# HighVoltageOutputMirror.net
KiCad netlist of a schematic drawn in EAGLE
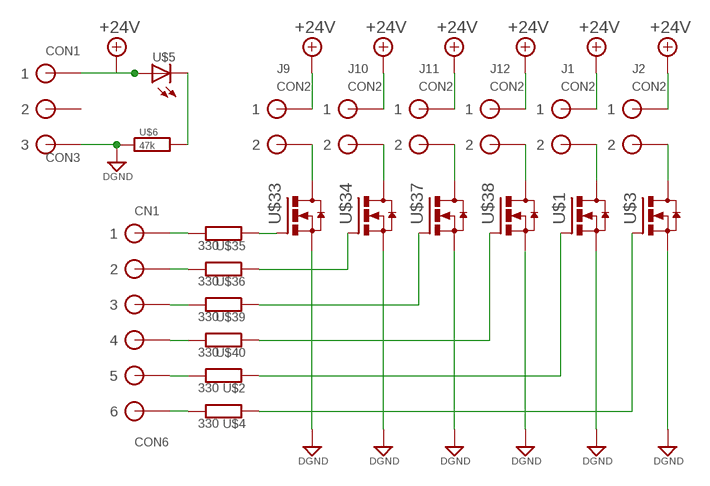
[diagram p0: schematic, sheet 1]

(export (version "E")
  (design (tool "Eeschema 10.0.6"))
  (components
    (comp (ref "CN1")
      (value "CON6")
      (footprint "eagle-import:CON6")
      (libsource (lib "eagle-import") (part "CON6"))
    )
    (comp (ref "CON1")
      (value "CON3")
      (footprint "eagle-import:CON3")
      (libsource (lib "eagle-import") (part "CON3"))
    )
    (comp (ref "J1")
      (value "CON2")
      (footprint "eagle-import:CON2")
      (libsource (lib "eagle-import") (part "CON2"))
    )
    (comp (ref "J2")
      (value "CON2")
      (footprint "eagle-import:CON2")
      (libsource (lib "eagle-import") (part "CON2"))
    )
    (comp (ref "J9")
      (value "CON2")
      (footprint "eagle-import:CON2")
      (libsource (lib "eagle-import") (part "CON2"))
    )
    (comp (ref "J10")
      (value "CON2")
      (footprint "eagle-import:CON2")
      (libsource (lib "eagle-import") (part "CON2"))
    )
    (comp (ref "J11")
      (value "CON2")
      (footprint "eagle-import:CON2")
      (libsource (lib "eagle-import") (part "CON2"))
    )
    (comp (ref "J12")
      (value "CON2")
      (footprint "eagle-import:CON2")
      (libsource (lib "eagle-import") (part "CON2"))
    )
    (comp (ref "U$1")
      (value "TO-252(MOS-FET_N)TO-252FORHAND")
      (footprint "eagle-import:TO-252FORHAND")
      (libsource (lib "eagle-import") (part "TO-252(MOS-FET_N)TO-252FORHAND"))
    )
    (comp (ref "U$2")
      (value "330")
      (footprint "eagle-import:1_4W-H4_(0207_10)")
      (libsource (lib "eagle-import") (part "抵抗0207/10"))
    )
    (comp (ref "U$3")
      (value "TO-252(MOS-FET_N)TO-252FORHAND")
      (footprint "eagle-import:TO-252FORHAND")
      (libsource (lib "eagle-import") (part "TO-252(MOS-FET_N)TO-252FORHAND"))
    )
    (comp (ref "U$4")
      (value "330")
      (footprint "eagle-import:1_4W-H4_(0207_10)")
      (libsource (lib "eagle-import") (part "抵抗0207/10"))
    )
    (comp (ref "U$5")
      (value "LED(砲弾型)3")
      (footprint "eagle-import:LED3MM")
      (libsource (lib "eagle-import") (part "LED(砲弾型)3"))
    )
    (comp (ref "U$6")
      (value "47k")
      (footprint "eagle-import:0805(JIS2012)HAND")
      (libsource (lib "eagle-import") (part "抵抗0805"))
    )
    (comp (ref "U$33")
      (value "TO-252(MOS-FET_N)TO-252FORHAND")
      (footprint "eagle-import:TO-252FORHAND")
      (libsource (lib "eagle-import") (part "TO-252(MOS-FET_N)TO-252FORHAND"))
    )
    (comp (ref "U$34")
      (value "TO-252(MOS-FET_N)TO-252FORHAND")
      (footprint "eagle-import:TO-252FORHAND")
      (libsource (lib "eagle-import") (part "TO-252(MOS-FET_N)TO-252FORHAND"))
    )
    (comp (ref "U$35")
      (value "330")
      (footprint "eagle-import:1_4W-H4_(0207_10)")
      (libsource (lib "eagle-import") (part "抵抗0207/10"))
    )
    (comp (ref "U$36")
      (value "330")
      (footprint "eagle-import:1_4W-H4_(0207_10)")
      (libsource (lib "eagle-import") (part "抵抗0207/10"))
    )
    (comp (ref "U$37")
      (value "TO-252(MOS-FET_N)TO-252FORHAND")
      (footprint "eagle-import:TO-252FORHAND")
      (libsource (lib "eagle-import") (part "TO-252(MOS-FET_N)TO-252FORHAND"))
    )
    (comp (ref "U$38")
      (value "TO-252(MOS-FET_N)TO-252FORHAND")
      (footprint "eagle-import:TO-252FORHAND")
      (libsource (lib "eagle-import") (part "TO-252(MOS-FET_N)TO-252FORHAND"))
    )
    (comp (ref "U$39")
      (value "330")
      (footprint "eagle-import:1_4W-H4_(0207_10)")
      (libsource (lib "eagle-import") (part "抵抗0207/10"))
    )
    (comp (ref "U$40")
      (value "330")
      (footprint "eagle-import:1_4W-H4_(0207_10)")
      (libsource (lib "eagle-import") (part "抵抗0207/10"))
    )
  )
  (nets
    (net (code "1") (name "+24V") (class "Default")
      (node (ref "CON1") (pin "P$1") (pinfunction "1_P$1") (pintype "bidirectional"))
      (node (ref "J1") (pin "P$1") (pinfunction "1_P$1") (pintype "bidirectional"))
      (node (ref "J10") (pin "P$1") (pinfunction "1_P$1") (pintype "bidirectional"))
      (node (ref "J11") (pin "P$1") (pinfunction "1_P$1") (pintype "bidirectional"))
      (node (ref "J12") (pin "P$1") (pinfunction "1_P$1") (pintype "bidirectional"))
      (node (ref "J2") (pin "P$1") (pinfunction "1_P$1") (pintype "bidirectional"))
      (node (ref "J9") (pin "P$1") (pinfunction "1_P$1") (pintype "bidirectional"))
      (node (ref "U$5") (pin "A") (pinfunction "A_A") (pintype "passive"))
    )
    (net (code "2") (name "DGND") (class "Default")
      (node (ref "CON1") (pin "P$3") (pinfunction "3_P$3") (pintype "bidirectional"))
      (node (ref "U$1") (pin "2") (pinfunction "S_2") (pintype "passive"))
      (node (ref "U$3") (pin "2") (pinfunction "S_2") (pintype "passive"))
      (node (ref "U$33") (pin "2") (pinfunction "S_2") (pintype "passive"))
      (node (ref "U$34") (pin "2") (pinfunction "S_2") (pintype "passive"))
      (node (ref "U$37") (pin "2") (pinfunction "S_2") (pintype "passive"))
      (node (ref "U$38") (pin "2") (pinfunction "S_2") (pintype "passive"))
      (node (ref "U$6") (pin "1") (pinfunction "1_1") (pintype "passive"))
    )
    (net (code "3") (name "Net-(CN1-1)") (class "Default")
      (node (ref "CN1") (pin "P$1") (pinfunction "1_P$1") (pintype "bidirectional"))
      (node (ref "U$35") (pin "2") (pinfunction "2_2") (pintype "passive"))
    )
    (net (code "4") (name "Net-(CN1-2)") (class "Default")
      (node (ref "CN1") (pin "P$2") (pinfunction "2_P$2") (pintype "bidirectional"))
      (node (ref "U$36") (pin "2") (pinfunction "2_2") (pintype "passive"))
    )
    (net (code "5") (name "Net-(CN1-3)") (class "Default")
      (node (ref "CN1") (pin "P$3") (pinfunction "3_P$3") (pintype "bidirectional"))
      (node (ref "U$39") (pin "2") (pinfunction "2_2") (pintype "passive"))
    )
    (net (code "6") (name "Net-(CN1-4)") (class "Default")
      (node (ref "CN1") (pin "P$4") (pinfunction "4_P$4") (pintype "bidirectional"))
      (node (ref "U$40") (pin "2") (pinfunction "2_2") (pintype "passive"))
    )
    (net (code "7") (name "Net-(CN1-5)") (class "Default")
      (node (ref "CN1") (pin "P$5") (pinfunction "5_P$5") (pintype "bidirectional"))
      (node (ref "U$2") (pin "2") (pinfunction "2_2") (pintype "passive"))
    )
    (net (code "8") (name "Net-(CN1-6)") (class "Default")
      (node (ref "CN1") (pin "P$6") (pinfunction "6_P$6") (pintype "bidirectional"))
      (node (ref "U$4") (pin "2") (pinfunction "2_2") (pintype "passive"))
    )
    (net (code "9") (name "Net-(J1-2)") (class "Default")
      (node (ref "J1") (pin "P$2") (pinfunction "2_P$2") (pintype "bidirectional"))
      (node (ref "U$1") (pin "3") (pinfunction "D_3") (pintype "passive"))
    )
    (net (code "10") (name "Net-(J2-2)") (class "Default")
      (node (ref "J2") (pin "P$2") (pinfunction "2_P$2") (pintype "bidirectional"))
      (node (ref "U$3") (pin "3") (pinfunction "D_3") (pintype "passive"))
    )
    (net (code "11") (name "Net-(J9-2)") (class "Default")
      (node (ref "J9") (pin "P$2") (pinfunction "2_P$2") (pintype "bidirectional"))
      (node (ref "U$33") (pin "3") (pinfunction "D_3") (pintype "passive"))
    )
    (net (code "12") (name "Net-(J10-2)") (class "Default")
      (node (ref "J10") (pin "P$2") (pinfunction "2_P$2") (pintype "bidirectional"))
      (node (ref "U$34") (pin "3") (pinfunction "D_3") (pintype "passive"))
    )
    (net (code "13") (name "Net-(J11-2)") (class "Default")
      (node (ref "J11") (pin "P$2") (pinfunction "2_P$2") (pintype "bidirectional"))
      (node (ref "U$37") (pin "3") (pinfunction "D_3") (pintype "passive"))
    )
    (net (code "14") (name "Net-(J12-2)") (class "Default")
      (node (ref "J12") (pin "P$2") (pinfunction "2_P$2") (pintype "bidirectional"))
      (node (ref "U$38") (pin "3") (pinfunction "D_3") (pintype "passive"))
    )
    (net (code "15") (name "Net-(U$1-G)") (class "Default")
      (node (ref "U$1") (pin "1") (pinfunction "G_1") (pintype "passive"))
      (node (ref "U$2") (pin "1") (pinfunction "1_1") (pintype "passive"))
    )
    (net (code "16") (name "Net-(U$3-G)") (class "Default")
      (node (ref "U$3") (pin "1") (pinfunction "G_1") (pintype "passive"))
      (node (ref "U$4") (pin "1") (pinfunction "1_1") (pintype "passive"))
    )
    (net (code "17") (name "Net-(U$5-PadK)") (class "Default")
      (node (ref "U$5") (pin "K") (pinfunction "K_K") (pintype "passive"))
      (node (ref "U$6") (pin "2") (pinfunction "2_2") (pintype "passive"))
    )
    (net (code "18") (name "Net-(U$33-G)") (class "Default")
      (node (ref "U$33") (pin "1") (pinfunction "G_1") (pintype "passive"))
      (node (ref "U$35") (pin "1") (pinfunction "1_1") (pintype "passive"))
    )
    (net (code "19") (name "Net-(U$34-G)") (class "Default")
      (node (ref "U$34") (pin "1") (pinfunction "G_1") (pintype "passive"))
      (node (ref "U$36") (pin "1") (pinfunction "1_1") (pintype "passive"))
    )
    (net (code "20") (name "Net-(U$37-G)") (class "Default")
      (node (ref "U$37") (pin "1") (pinfunction "G_1") (pintype "passive"))
      (node (ref "U$39") (pin "1") (pinfunction "1_1") (pintype "passive"))
    )
    (net (code "21") (name "Net-(U$38-G)") (class "Default")
      (node (ref "U$38") (pin "1") (pinfunction "G_1") (pintype "passive"))
      (node (ref "U$40") (pin "1") (pinfunction "1_1") (pintype "passive"))
    )
    (net (code "22") (name "unconnected-(CON1-2-PadP$2)") (class "Default")
      (node (ref "CON1") (pin "P$2") (pinfunction "2_P$2") (pintype "bidirectional"))
    )
  )
)
